# MCU.net
KiCad netlist of a schematic drawn in Altium Designer
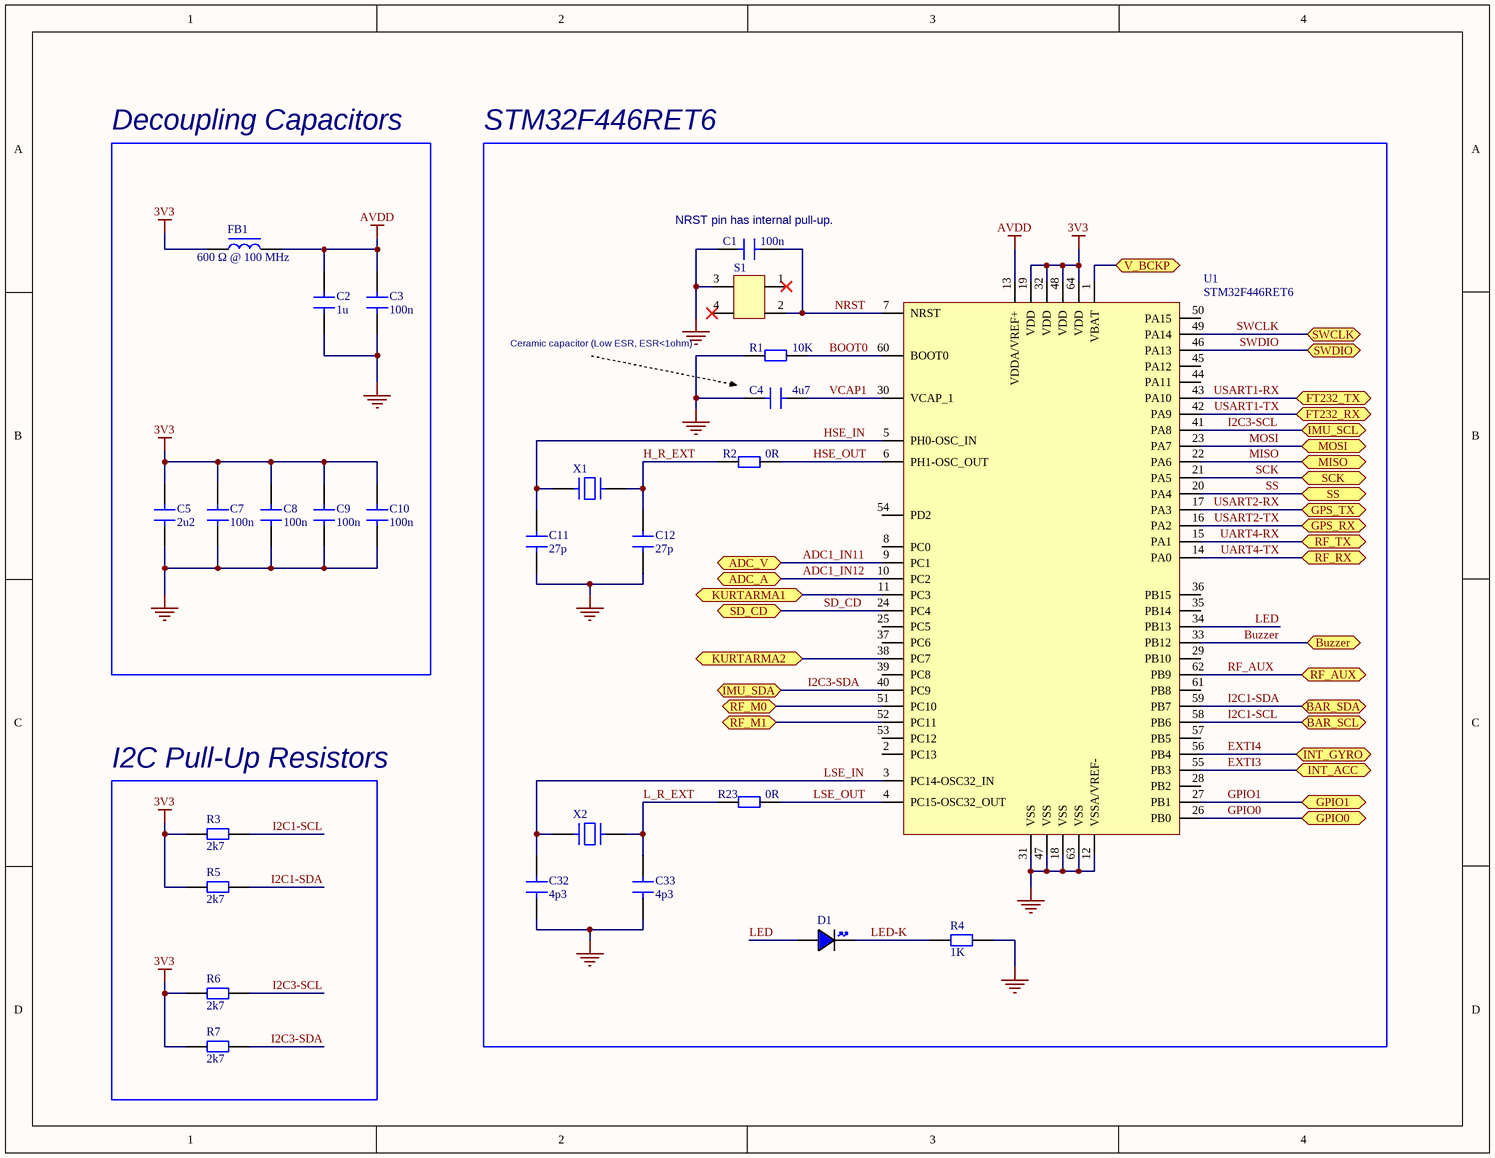
[diagram p0: MCU.SchDoc]

(export (version "E")
  (design (tool "Eeschema 10.0.6"))
  (components
    (comp (ref "C1")
      (value "100n")
      (footprint "CAP 0603")
      (description "Capacitor SMD 0603 50V")
      (libsource (lib "Schlib") (part "CAP 0603 50V"))
    )
    (comp (ref "C2")
      (value "1u")
      (footprint "CAP 0805")
      (description "Capacitor SMD 0805 50V")
      (libsource (lib "Schlib") (part "CAP 0805 50V"))
    )
    (comp (ref "C3")
      (value "100n")
      (footprint "CAP 0603")
      (description "Capacitor SMD 0603 50V")
      (libsource (lib "Schlib") (part "CAP 0603 50V"))
    )
    (comp (ref "C4")
      (value "4u7")
      (footprint "CAP 0805")
      (description "Capacitor SMD 0805 25V")
      (libsource (lib "Schlib") (part "CAP 0805 25V"))
    )
    (comp (ref "C5")
      (value "2u2")
      (footprint "CAP 0805")
      (description "Capacitor SMD 0805 25V")
      (libsource (lib "Schlib") (part "CAP 0805 25V"))
    )
    (comp (ref "C7")
      (value "100n")
      (footprint "CAP 0603")
      (description "Capacitor SMD 0603 50V")
      (libsource (lib "Schlib") (part "CAP 0603 50V"))
    )
    (comp (ref "C8")
      (value "100n")
      (footprint "CAP 0603")
      (description "Capacitor SMD 0603 50V")
      (libsource (lib "Schlib") (part "CAP 0603 50V"))
    )
    (comp (ref "C9")
      (value "100n")
      (footprint "CAP 0603")
      (description "Capacitor SMD 0603 50V")
      (libsource (lib "Schlib") (part "CAP 0603 50V"))
    )
    (comp (ref "C10")
      (value "100n")
      (footprint "CAP 0603")
      (description "Capacitor SMD 0603 50V")
      (libsource (lib "Schlib") (part "CAP 0603 50V"))
    )
    (comp (ref "C11")
      (value "27p")
      (footprint "CAP 0603")
      (description "Capacitor SMD 0603 50V")
      (libsource (lib "Schlib") (part "CAP 0603 50V"))
    )
    (comp (ref "C12")
      (value "27p")
      (footprint "CAP 0603")
      (description "Capacitor SMD 0603 50V")
      (libsource (lib "Schlib") (part "CAP 0603 50V"))
    )
    (comp (ref "C32")
      (value "4p3")
      (footprint "CAP 0603")
      (description "Capacitor SMD 0603 50V")
      (libsource (lib "Schlib") (part "CAP 0603 50V"))
    )
    (comp (ref "C33")
      (value "4p3")
      (footprint "CAP 0603")
      (description "Capacitor SMD 0603 50V")
      (libsource (lib "Schlib") (part "CAP 0603 50V"))
    )
    (comp (ref "D1")
      (value "LED 0805 BLUE")
      (footprint "LED 0805 BLUE")
      (description "LED 0805 BLUE SMD")
      (libsource (lib "Schlib") (part "LED 0805 BLUE"))
    )
    (comp (ref "FB1")
      (value "600 Ω @ 100 MHz")
      (footprint "FB 0805")
      (description "Ferrite Bead SMD 0805")
      (libsource (lib "Schlib") (part "FB 0805"))
    )
    (comp (ref "R1")
      (value "10K")
      (footprint "RES 0603")
      (description "Resistor SMD 0603")
      (libsource (lib "Schlib") (part "RES 0603"))
    )
    (comp (ref "R2")
      (value "0R")
      (footprint "RES 0603")
      (description "Resistor SMD 0603")
      (libsource (lib "Schlib") (part "RES 0603"))
    )
    (comp (ref "R3")
      (value "2k7")
      (footprint "RES 0603")
      (description "Resistor SMD 0603")
      (libsource (lib "Schlib") (part "RES 0603"))
    )
    (comp (ref "R4")
      (value "1K")
      (footprint "RES 0603")
      (description "Resistor SMD 0603")
      (libsource (lib "Schlib") (part "RES 0603"))
    )
    (comp (ref "R5")
      (value "2k7")
      (footprint "RES 0603")
      (description "Resistor SMD 0603")
      (libsource (lib "Schlib") (part "RES 0603"))
    )
    (comp (ref "R6")
      (value "2k7")
      (footprint "RES 0603")
      (description "Resistor SMD 0603")
      (libsource (lib "Schlib") (part "RES 0603"))
    )
    (comp (ref "R7")
      (value "2k7")
      (footprint "RES 0603")
      (description "Resistor SMD 0603")
      (libsource (lib "Schlib") (part "RES 0603"))
    )
    (comp (ref "R23")
      (value "0R")
      (footprint "RES 0603")
      (description "Resistor SMD 0603")
      (libsource (lib "Schlib") (part "RES 0603"))
    )
    (comp (ref "S1")
      (value "FSM4JSMATR")
      (footprint "FSM4JSMATR")
      (description "Switch Tactile OFF (ON) SPST Round Button Gull Wing 0.05A 24VDC 1.57N SMD T/R")
      (fields (field (name "MANUFACTURER") "TE Connectivity Alcoswitch"))
      (libsource (lib "Schlib") (part "FSM4JSMATR"))
    )
    (comp (ref "U1")
      (value "STM32F446RET6")
      (footprint "STM32F446RET6")
      (description "ARM® Cortex®-M4 STM32 F4 Microcontroller IC 32-Bit 180MHz 512KB (512K x 8) FLASH 64-LQFP (10x10)")
      (fields (field (name "MANUFACTURER") "STMicroelectronics"))
      (libsource (lib "Schlib") (part "STM32F446RET6"))
    )
    (comp (ref "X1")
      (value "ABM3-8.000MHZ-D2Y-T")
      (footprint "ABM3-8.000MHZ-D2Y-T")
      (description "Crystal 8MHz ±20ppm (Tol) ±30ppm (Stability) 18pF FUND 140Ohm 2-Pin Mini-CSMD T/R")
      (fields (field (name "MANUFACTURER") "Abracon"))
      (libsource (lib "Schlib") (part "ABM3-8.000MHZ-D2Y-T"))
    )
    (comp (ref "X2")
      (value "ABS25-32.768KHZ-6-T")
      (footprint "ABS25-32.768KHZ-6-T")
      (description "Crystal, Plastic Molded 32.768Khz, 6Pf, 20Ppm-40+85C, 8 X 3.8 X 2.5 Rohs Compliant: Yes")
      (fields (field (name "MANUFACTURER") "Abracon"))
      (libsource (lib "Schlib") (part "ABS25-32.768KHZ-6-T"))
    )
  )
  (nets
    (net (code "1") (name "/ADC1_IN11") (class "Default")
      (node (ref "U1") (pin "9") (pinfunction "PC1_9") (pintype "passive"))
    )
    (net (code "2") (name "/ADC1_IN12") (class "Default")
      (node (ref "U1") (pin "10") (pinfunction "PC2_10") (pintype "passive"))
    )
    (net (code "3") (name "/BOOT0") (class "Default")
      (node (ref "R1") (pin "2") (pinfunction "2_2") (pintype "passive"))
      (node (ref "U1") (pin "60") (pinfunction "BOOT0_60") (pintype "passive"))
    )
    (net (code "4") (name "/Buzzer") (class "Default")
      (node (ref "U1") (pin "33") (pinfunction "PB12_33") (pintype "passive"))
    )
    (net (code "5") (name "/EXTI3") (class "Default")
      (node (ref "U1") (pin "55") (pinfunction "PB3_55") (pintype "passive"))
    )
    (net (code "6") (name "/EXTI4") (class "Default")
      (node (ref "U1") (pin "56") (pinfunction "PB4_56") (pintype "passive"))
    )
    (net (code "7") (name "/GPIO0") (class "Default")
      (node (ref "U1") (pin "26") (pinfunction "PB0_26") (pintype "passive"))
    )
    (net (code "8") (name "/GPIO1") (class "Default")
      (node (ref "U1") (pin "27") (pinfunction "PB1_27") (pintype "passive"))
    )
    (net (code "9") (name "/HSE_IN") (class "Default")
      (node (ref "C11") (pin "2") (pinfunction "2_2") (pintype "passive"))
      (node (ref "U1") (pin "5") (pinfunction "PH0-OSC_IN_5") (pintype "passive"))
      (node (ref "X1") (pin "1") (pinfunction "1_1") (pintype "passive"))
    )
    (net (code "10") (name "/HSE_OUT") (class "Default")
      (node (ref "R2") (pin "2") (pinfunction "2_2") (pintype "passive"))
      (node (ref "U1") (pin "6") (pinfunction "PH1-OSC_OUT_6") (pintype "passive"))
    )
    (net (code "11") (name "/H_R_EXT") (class "Default")
      (node (ref "C12") (pin "2") (pinfunction "2_2") (pintype "passive"))
      (node (ref "R2") (pin "1") (pinfunction "1_1") (pintype "passive"))
      (node (ref "X1") (pin "2") (pinfunction "2_2") (pintype "passive"))
    )
    (net (code "12") (name "/I2C1-SCL") (class "Default")
      (node (ref "R3") (pin "1") (pinfunction "1_1") (pintype "passive"))
      (node (ref "U1") (pin "58") (pinfunction "PB6_58") (pintype "passive"))
    )
    (net (code "13") (name "/I2C1-SDA") (class "Default")
      (node (ref "R5") (pin "1") (pinfunction "1_1") (pintype "passive"))
      (node (ref "U1") (pin "59") (pinfunction "PB7_59") (pintype "passive"))
    )
    (net (code "14") (name "/I2C3-SCL") (class "Default")
      (node (ref "R6") (pin "1") (pinfunction "1_1") (pintype "passive"))
      (node (ref "U1") (pin "41") (pinfunction "PA8_41") (pintype "passive"))
    )
    (net (code "15") (name "/I2C3-SDA") (class "Default")
      (node (ref "R7") (pin "1") (pinfunction "1_1") (pintype "passive"))
      (node (ref "U1") (pin "40") (pinfunction "PC9_40") (pintype "passive"))
    )
    (net (code "16") (name "/KURTARMA1") (class "Default")
      (node (ref "U1") (pin "11") (pinfunction "PC3_11") (pintype "passive"))
    )
    (net (code "17") (name "/KURTARMA2") (class "Default")
      (node (ref "U1") (pin "38") (pinfunction "PC7_38") (pintype "passive"))
    )
    (net (code "18") (name "/LED") (class "Default")
      (node (ref "D1") (pin "A") (pinfunction "A_A") (pintype "passive"))
      (node (ref "U1") (pin "34") (pinfunction "PB13_34") (pintype "passive"))
    )
    (net (code "19") (name "/LED-K") (class "Default")
      (node (ref "D1") (pin "K") (pinfunction "K_K") (pintype "passive"))
      (node (ref "R4") (pin "1") (pinfunction "1_1") (pintype "passive"))
    )
    (net (code "20") (name "/LSE_IN") (class "Default")
      (node (ref "C32") (pin "2") (pinfunction "2_2") (pintype "passive"))
      (node (ref "U1") (pin "3") (pinfunction "PC14-OSC32_IN_3") (pintype "passive"))
      (node (ref "X2") (pin "1") (pinfunction "1_1") (pintype "passive"))
    )
    (net (code "21") (name "/LSE_OUT") (class "Default")
      (node (ref "R23") (pin "2") (pinfunction "2_2") (pintype "passive"))
      (node (ref "U1") (pin "4") (pinfunction "PC15-OSC32_OUT_4") (pintype "passive"))
    )
    (net (code "22") (name "/L_R_EXT") (class "Default")
      (node (ref "C33") (pin "2") (pinfunction "2_2") (pintype "passive"))
      (node (ref "R23") (pin "1") (pinfunction "1_1") (pintype "passive"))
      (node (ref "X2") (pin "4") (pinfunction "4_4") (pintype "passive"))
    )
    (net (code "23") (name "/MISO") (class "Default")
      (node (ref "U1") (pin "22") (pinfunction "PA6_22") (pintype "passive"))
    )
    (net (code "24") (name "/MOSI") (class "Default")
      (node (ref "U1") (pin "23") (pinfunction "PA7_23") (pintype "passive"))
    )
    (net (code "25") (name "/NRST") (class "Default")
      (node (ref "C1") (pin "2") (pinfunction "2_2") (pintype "passive"))
      (node (ref "S1") (pin "2") (pinfunction "2_2") (pintype "passive"))
      (node (ref "U1") (pin "7") (pinfunction "NRST_7") (pintype "passive"))
    )
    (net (code "26") (name "/RF_AUX") (class "Default")
      (node (ref "U1") (pin "62") (pinfunction "PB9_62") (pintype "passive"))
    )
    (net (code "27") (name "/RF_M0") (class "Default")
      (node (ref "U1") (pin "51") (pinfunction "PC10_51") (pintype "passive"))
    )
    (net (code "28") (name "/RF_M1") (class "Default")
      (node (ref "U1") (pin "52") (pinfunction "PC11_52") (pintype "passive"))
    )
    (net (code "29") (name "/SCK") (class "Default")
      (node (ref "U1") (pin "21") (pinfunction "PA5_21") (pintype "passive"))
    )
    (net (code "30") (name "/SD_CD") (class "Default")
      (node (ref "U1") (pin "24") (pinfunction "PC4_24") (pintype "passive"))
    )
    (net (code "31") (name "/SS") (class "Default")
      (node (ref "U1") (pin "20") (pinfunction "PA4_20") (pintype "passive"))
    )
    (net (code "32") (name "/SWCLK") (class "Default")
      (node (ref "U1") (pin "49") (pinfunction "PA14_49") (pintype "passive"))
    )
    (net (code "33") (name "/SWDIO") (class "Default")
      (node (ref "U1") (pin "46") (pinfunction "PA13_46") (pintype "passive"))
    )
    (net (code "34") (name "/UART4-RX") (class "Default")
      (node (ref "U1") (pin "15") (pinfunction "PA1_15") (pintype "passive"))
    )
    (net (code "35") (name "/UART4-TX") (class "Default")
      (node (ref "U1") (pin "14") (pinfunction "PA0_14") (pintype "passive"))
    )
    (net (code "36") (name "/USART1-RX") (class "Default")
      (node (ref "U1") (pin "43") (pinfunction "PA10_43") (pintype "passive"))
    )
    (net (code "37") (name "/USART1-TX") (class "Default")
      (node (ref "U1") (pin "42") (pinfunction "PA9_42") (pintype "passive"))
    )
    (net (code "38") (name "/USART2-RX") (class "Default")
      (node (ref "U1") (pin "17") (pinfunction "PA3_17") (pintype "passive"))
    )
    (net (code "39") (name "/USART2-TX") (class "Default")
      (node (ref "U1") (pin "16") (pinfunction "PA2_16") (pintype "passive"))
    )
    (net (code "40") (name "/VCAP1") (class "Default")
      (node (ref "C4") (pin "2") (pinfunction "2_2") (pintype "passive"))
      (node (ref "U1") (pin "30") (pinfunction "VCAP_1_30") (pintype "passive"))
    )
    (net (code "41") (name "/V_BCKP") (class "Default")
      (node (ref "U1") (pin "1") (pinfunction "VBAT_1") (pintype "passive"))
    )
    (net (code "42") (name "3V3") (class "Default")
      (node (ref "C10") (pin "2") (pinfunction "2_2") (pintype "passive"))
      (node (ref "C5") (pin "2") (pinfunction "2_2") (pintype "passive"))
      (node (ref "C7") (pin "2") (pinfunction "2_2") (pintype "passive"))
      (node (ref "C8") (pin "2") (pinfunction "2_2") (pintype "passive"))
      (node (ref "C9") (pin "2") (pinfunction "2_2") (pintype "passive"))
      (node (ref "FB1") (pin "1") (pintype "passive"))
      (node (ref "R3") (pin "2") (pinfunction "2_2") (pintype "passive"))
      (node (ref "R5") (pin "2") (pinfunction "2_2") (pintype "passive"))
      (node (ref "R6") (pin "2") (pinfunction "2_2") (pintype "passive"))
      (node (ref "R7") (pin "2") (pinfunction "2_2") (pintype "passive"))
      (node (ref "U1") (pin "19") (pinfunction "VDD_19") (pintype "passive"))
      (node (ref "U1") (pin "32") (pinfunction "VDD_32") (pintype "passive"))
      (node (ref "U1") (pin "48") (pinfunction "VDD_48") (pintype "passive"))
      (node (ref "U1") (pin "64") (pinfunction "VDD_64") (pintype "passive"))
    )
    (net (code "43") (name "AVDD") (class "Default")
      (node (ref "C2") (pin "2") (pinfunction "2_2") (pintype "passive"))
      (node (ref "C3") (pin "2") (pinfunction "2_2") (pintype "passive"))
      (node (ref "FB1") (pin "2") (pintype "passive"))
      (node (ref "U1") (pin "13") (pinfunction "VDDA/VREF+_13") (pintype "passive"))
    )
    (net (code "44") (name "GND") (class "Default")
      (node (ref "C1") (pin "1") (pinfunction "1_1") (pintype "passive"))
      (node (ref "C10") (pin "1") (pinfunction "1_1") (pintype "passive"))
      (node (ref "C11") (pin "1") (pinfunction "1_1") (pintype "passive"))
      (node (ref "C12") (pin "1") (pinfunction "1_1") (pintype "passive"))
      (node (ref "C2") (pin "1") (pinfunction "1_1") (pintype "passive"))
      (node (ref "C3") (pin "1") (pinfunction "1_1") (pintype "passive"))
      (node (ref "C32") (pin "1") (pinfunction "1_1") (pintype "passive"))
      (node (ref "C33") (pin "1") (pinfunction "1_1") (pintype "passive"))
      (node (ref "C4") (pin "1") (pinfunction "1_1") (pintype "passive"))
      (node (ref "C5") (pin "1") (pinfunction "1_1") (pintype "passive"))
      (node (ref "C7") (pin "1") (pinfunction "1_1") (pintype "passive"))
      (node (ref "C8") (pin "1") (pinfunction "1_1") (pintype "passive"))
      (node (ref "C9") (pin "1") (pinfunction "1_1") (pintype "passive"))
      (node (ref "R1") (pin "1") (pinfunction "1_1") (pintype "passive"))
      (node (ref "R4") (pin "2") (pinfunction "2_2") (pintype "passive"))
      (node (ref "S1") (pin "3") (pinfunction "3_3") (pintype "passive"))
      (node (ref "U1") (pin "12") (pinfunction "VSSA/VREF-_12") (pintype "passive"))
      (node (ref "U1") (pin "18") (pinfunction "VSS_18") (pintype "passive"))
      (node (ref "U1") (pin "31") (pinfunction "VSS_31") (pintype "passive"))
      (node (ref "U1") (pin "47") (pinfunction "VSS_47") (pintype "passive"))
      (node (ref "U1") (pin "63") (pinfunction "VSS_63") (pintype "passive"))
    )
    (net (code "45") (name "unconnected-(S1-Pad1)") (class "Default")
      (node (ref "S1") (pin "1") (pinfunction "1_1") (pintype "passive+no_connect"))
    )
    (net (code "46") (name "unconnected-(S1-Pad4)") (class "Default")
      (node (ref "S1") (pin "4") (pinfunction "4_4") (pintype "passive+no_connect"))
    )
    (net (code "47") (name "unconnected-(U1-PA11-Pad44)") (class "Default")
      (node (ref "U1") (pin "44") (pinfunction "PA11_44") (pintype "passive"))
    )
    (net (code "48") (name "unconnected-(U1-PA12-Pad45)") (class "Default")
      (node (ref "U1") (pin "45") (pinfunction "PA12_45") (pintype "passive"))
    )
    (net (code "49") (name "unconnected-(U1-PA15-Pad50)") (class "Default")
      (node (ref "U1") (pin "50") (pinfunction "PA15_50") (pintype "passive"))
    )
    (net (code "50") (name "unconnected-(U1-PB2-Pad28)") (class "Default")
      (node (ref "U1") (pin "28") (pinfunction "PB2_28") (pintype "passive"))
    )
    (net (code "51") (name "unconnected-(U1-PB5-Pad57)") (class "Default")
      (node (ref "U1") (pin "57") (pinfunction "PB5_57") (pintype "passive"))
    )
    (net (code "52") (name "unconnected-(U1-PB8-Pad61)") (class "Default")
      (node (ref "U1") (pin "61") (pinfunction "PB8_61") (pintype "passive"))
    )
    (net (code "53") (name "unconnected-(U1-PB10-Pad29)") (class "Default")
      (node (ref "U1") (pin "29") (pinfunction "PB10_29") (pintype "passive"))
    )
    (net (code "54") (name "unconnected-(U1-PB14-Pad35)") (class "Default")
      (node (ref "U1") (pin "35") (pinfunction "PB14_35") (pintype "passive"))
    )
    (net (code "55") (name "unconnected-(U1-PB15-Pad36)") (class "Default")
      (node (ref "U1") (pin "36") (pinfunction "PB15_36") (pintype "passive"))
    )
    (net (code "56") (name "unconnected-(U1-PC0-Pad8)") (class "Default")
      (node (ref "U1") (pin "8") (pinfunction "PC0_8") (pintype "passive"))
    )
    (net (code "57") (name "unconnected-(U1-PC5-Pad25)") (class "Default")
      (node (ref "U1") (pin "25") (pinfunction "PC5_25") (pintype "passive"))
    )
    (net (code "58") (name "unconnected-(U1-PC6-Pad37)") (class "Default")
      (node (ref "U1") (pin "37") (pinfunction "PC6_37") (pintype "passive"))
    )
    (net (code "59") (name "unconnected-(U1-PC8-Pad39)") (class "Default")
      (node (ref "U1") (pin "39") (pinfunction "PC8_39") (pintype "passive"))
    )
    (net (code "60") (name "unconnected-(U1-PC12-Pad53)") (class "Default")
      (node (ref "U1") (pin "53") (pinfunction "PC12_53") (pintype "passive"))
    )
    (net (code "61") (name "unconnected-(U1-PC13-Pad2)") (class "Default")
      (node (ref "U1") (pin "2") (pinfunction "PC13_2") (pintype "passive"))
    )
    (net (code "62") (name "unconnected-(U1-PD2-Pad54)") (class "Default")
      (node (ref "U1") (pin "54") (pinfunction "PD2_54") (pintype "passive"))
    )
  )
)
